# DSP_Header.net
KiCad netlist of a schematic drawn in Altium Designer
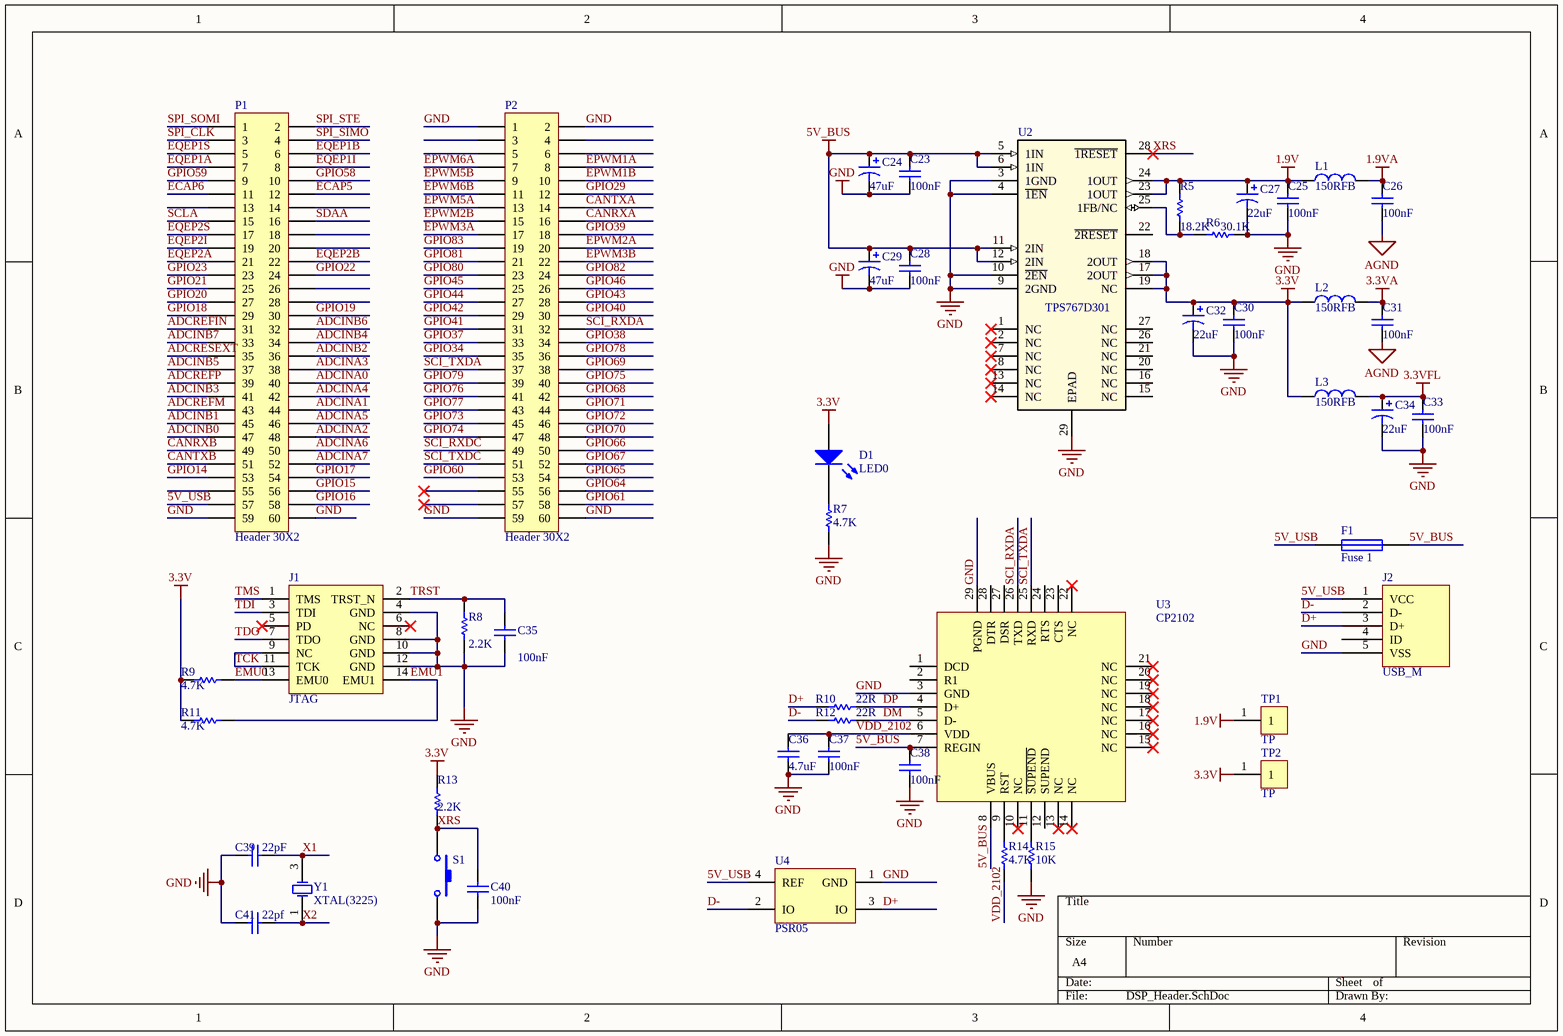
[diagram p0: DSP_Header.SchDoc]

(export (version "E")
  (design (tool "Eeschema 10.0.6"))
  (components
    (comp (ref "C23")
      (value "100nF")
      (footprint "C0603")
      (description "Capacitor")
      (fields (field (name "Comment") "Cap") (field (name "PUBLISHER") "Altium Limited"))
      (libsource (lib "Miscellaneous Devices") (part "Cap"))
    )
    (comp (ref "C24")
      (value "47uF")
      (footprint "C0805")
      (description "Polarized Capacitor (Surface Mount)")
      (fields (field (name "Comment") "Cap Pol3") (field (name "PUBLISHER") "Altium Limited"))
      (libsource (lib "Miscellaneous Devices") (part "Cap Pol3"))
    )
    (comp (ref "C25")
      (value "100nF")
      (footprint "C0603")
      (description "Capacitor")
      (fields (field (name "Comment") "Cap") (field (name "PUBLISHER") "Altium Limited"))
      (libsource (lib "Miscellaneous Devices") (part "Cap"))
    )
    (comp (ref "C26")
      (value "100nF")
      (footprint "C0603")
      (description "Capacitor")
      (fields (field (name "Comment") "Cap") (field (name "PUBLISHER") "Altium Limited"))
      (libsource (lib "Miscellaneous Devices") (part "Cap"))
    )
    (comp (ref "C27")
      (value "22uF")
      (footprint "C0805")
      (description "Polarized Capacitor (Surface Mount)")
      (fields (field (name "Comment") "Cap Pol3") (field (name "PUBLISHER") "Altium Limited"))
      (libsource (lib "Miscellaneous Devices") (part "Cap Pol3"))
    )
    (comp (ref "C28")
      (value "100nF")
      (footprint "C0603")
      (description "Capacitor")
      (fields (field (name "Comment") "Cap") (field (name "PUBLISHER") "Altium Limited"))
      (libsource (lib "Miscellaneous Devices") (part "Cap"))
    )
    (comp (ref "C29")
      (value "47uF")
      (footprint "C0805")
      (description "Polarized Capacitor (Surface Mount)")
      (fields (field (name "Comment") "Cap Pol3") (field (name "PUBLISHER") "Altium Limited"))
      (libsource (lib "Miscellaneous Devices") (part "Cap Pol3"))
    )
    (comp (ref "C30")
      (value "100nF")
      (footprint "C0603")
      (description "Capacitor")
      (fields (field (name "Comment") "Cap") (field (name "PUBLISHER") "Altium Limited"))
      (libsource (lib "Miscellaneous Devices") (part "Cap"))
    )
    (comp (ref "C31")
      (value "100nF")
      (footprint "C0603")
      (description "Capacitor")
      (fields (field (name "Comment") "Cap") (field (name "PUBLISHER") "Altium Limited"))
      (libsource (lib "Miscellaneous Devices") (part "Cap"))
    )
    (comp (ref "C32")
      (value "22uF")
      (footprint "C0805")
      (description "Polarized Capacitor (Surface Mount)")
      (fields (field (name "Comment") "Cap Pol3") (field (name "PUBLISHER") "Altium Limited"))
      (libsource (lib "Miscellaneous Devices") (part "Cap Pol3"))
    )
    (comp (ref "C33")
      (value "100nF")
      (footprint "C0603")
      (description "Capacitor")
      (fields (field (name "Comment") "Cap") (field (name "PUBLISHER") "Altium Limited"))
      (libsource (lib "Miscellaneous Devices") (part "Cap"))
    )
    (comp (ref "C34")
      (value "22uF")
      (footprint "C0805")
      (description "Polarized Capacitor (Surface Mount)")
      (fields (field (name "Comment") "Cap Pol3") (field (name "PUBLISHER") "Altium Limited"))
      (libsource (lib "Miscellaneous Devices") (part "Cap Pol3"))
    )
    (comp (ref "C35")
      (value "100nF")
      (footprint "C0603")
      (description "Capacitor")
      (fields (field (name "Comment") "Cap") (field (name "PUBLISHER") "Altium Limited"))
      (libsource (lib "Miscellaneous Devices") (part "Cap"))
    )
    (comp (ref "C36")
      (value "4.7uF")
      (footprint "C0603")
      (description "Capacitor")
      (fields (field (name "Comment") "Cap") (field (name "PUBLISHER") "Altium Limited"))
      (libsource (lib "Miscellaneous Devices") (part "Cap"))
    )
    (comp (ref "C37")
      (value "100nF")
      (footprint "C0603")
      (description "Capacitor")
      (fields (field (name "Comment") "Cap") (field (name "PUBLISHER") "Altium Limited"))
      (libsource (lib "Miscellaneous Devices") (part "Cap"))
    )
    (comp (ref "C38")
      (value "100nF")
      (footprint "C0603")
      (description "Capacitor")
      (fields (field (name "Comment") "Cap") (field (name "PUBLISHER") "Altium Limited"))
      (libsource (lib "Miscellaneous Devices") (part "Cap"))
    )
    (comp (ref "C39")
      (value "22pF")
      (footprint "C0603")
      (description "Capacitor")
      (fields (field (name "Comment") "Cap") (field (name "PUBLISHER") "Altium Limited"))
      (libsource (lib "Miscellaneous Devices") (part "Cap"))
    )
    (comp (ref "C40")
      (value "100nF")
      (footprint "C0603")
      (description "Capacitor")
      (fields (field (name "Comment") "Cap") (field (name "PUBLISHER") "Altium Limited"))
      (libsource (lib "Miscellaneous Devices") (part "Cap"))
    )
    (comp (ref "C41")
      (value "22pf")
      (footprint "C0603")
      (description "Capacitor")
      (fields (field (name "Comment") "Cap") (field (name "PUBLISHER") "Altium Limited"))
      (libsource (lib "Miscellaneous Devices") (part "Cap"))
    )
    (comp (ref "D1")
      (value "LED0")
      (footprint "0603D")
      (description "Typical INFRARED GaAs LED")
      (fields (field (name "PUBLISHER") "Altium Limited"))
      (libsource (lib "Miscellaneous Devices") (part "LED0"))
    )
    (comp (ref "F1")
      (value "Fuse 1")
      (footprint "0805R")
      (description "Fuse")
      (fields (field (name "PUBLISHER") "Altium Limited"))
      (libsource (lib "Miscellaneous Devices") (part "Fuse 1"))
    )
    (comp (ref "J1") (value "JTAG") (footprint "HDR2X7") (libsource (lib "schlib_by_wjy") (part "JTAG")))
    (comp (ref "J2")
      (value "USB_M")
      (footprint "USB_MICRO_DIP")
      (description "MicroUSB接口")
      (libsource (lib "Fszhang") (part "USB_M"))
    )
    (comp (ref "L1")
      (value "150RFB")
      (footprint "r0603")
      (fields (field (name "Comment") "Inductors"))
      (libsource (lib "schlib_by_wjy") (part "Inductors"))
    )
    (comp (ref "L2")
      (value "150RFB")
      (footprint "r0603")
      (fields (field (name "Comment") "Inductors"))
      (libsource (lib "schlib_by_wjy") (part "Inductors"))
    )
    (comp (ref "L3")
      (value "150RFB")
      (footprint "r0603")
      (fields (field (name "Comment") "Inductors"))
      (libsource (lib "schlib_by_wjy") (part "Inductors"))
    )
    (comp (ref "P1")
      (value "Header 30X2")
      (footprint "0.8BTB_60P")
      (description "Header, 30-Pin, Dual row")
      (fields (field (name "PUBLISHER") "Altium Limited"))
      (libsource (lib "Miscellaneous Connectors") (part "Header 30X2"))
    )
    (comp (ref "P2")
      (value "Header 30X2")
      (footprint "0.8BTB_60P")
      (description "Header, 30-Pin, Dual row")
      (fields (field (name "PUBLISHER") "Altium Limited"))
      (libsource (lib "Miscellaneous Connectors") (part "Header 30X2"))
    )
    (comp (ref "R5")
      (value "18.2K")
      (footprint "r0603")
      (description "Resistor")
      (fields (field (name "Comment") "Res1") (field (name "PUBLISHER") "Altium Limited"))
      (libsource (lib "Miscellaneous Devices") (part "Res1"))
    )
    (comp (ref "R6")
      (value "30.1K")
      (footprint "r0603")
      (description "Resistor")
      (fields (field (name "Comment") "Res1") (field (name "PUBLISHER") "Altium Limited"))
      (libsource (lib "Miscellaneous Devices") (part "Res1"))
    )
    (comp (ref "R7")
      (value "4.7K")
      (footprint "R0603")
      (description "Resistor")
      (fields (field (name "Comment") "Res1") (field (name "PUBLISHER") "Altium Limited"))
      (libsource (lib "Miscellaneous Devices") (part "Res1"))
    )
    (comp (ref "R8")
      (value "2.2K")
      (footprint "r0603")
      (description "Resistor")
      (fields (field (name "Comment") "Res1") (field (name "PUBLISHER") "Altium Limited"))
      (libsource (lib "Miscellaneous Devices") (part "Res1"))
    )
    (comp (ref "R9")
      (value "4.7K")
      (footprint "R0603")
      (description "Resistor")
      (fields (field (name "Comment") "Res1") (field (name "PUBLISHER") "Altium Limited"))
      (libsource (lib "Miscellaneous Devices") (part "Res1"))
    )
    (comp (ref "R10")
      (value "22R")
      (footprint "R0603")
      (description "Resistor")
      (fields (field (name "Comment") "Res1") (field (name "PUBLISHER") "Altium Limited"))
      (libsource (lib "Miscellaneous Devices") (part "Res1"))
    )
    (comp (ref "R11")
      (value "4.7K")
      (footprint "r0603")
      (description "Resistor")
      (fields (field (name "Comment") "Res1") (field (name "PUBLISHER") "Altium Limited"))
      (libsource (lib "Miscellaneous Devices") (part "Res1"))
    )
    (comp (ref "R12")
      (value "22R")
      (footprint "R0603")
      (description "Resistor")
      (fields (field (name "Comment") "Res1") (field (name "PUBLISHER") "Altium Limited"))
      (libsource (lib "Miscellaneous Devices") (part "Res1"))
    )
    (comp (ref "R13")
      (value "2.2K")
      (footprint "r0603")
      (description "Resistor")
      (fields (field (name "Comment") "Res1") (field (name "PUBLISHER") "Altium Limited"))
      (libsource (lib "Miscellaneous Devices") (part "Res1"))
    )
    (comp (ref "R14")
      (value "4.7K")
      (footprint "R0603")
      (description "Resistor")
      (fields (field (name "Comment") "Res1") (field (name "PUBLISHER") "Altium Limited"))
      (libsource (lib "Miscellaneous Devices") (part "Res1"))
    )
    (comp (ref "R15")
      (value "10K")
      (footprint "R0603")
      (description "Resistor")
      (fields (field (name "Comment") "Res1") (field (name "PUBLISHER") "Altium Limited"))
      (libsource (lib "Miscellaneous Devices") (part "Res1"))
    )
    (comp (ref "S1")
      (value "SW-PB")
      (footprint "SW_3*6")
      (description "Switch")
      (fields (field (name "PUBLISHER") "Altium Limited"))
      (libsource (lib "Miscellaneous Devices") (part "SW-PB"))
    )
    (comp (ref "TP1") (value "TP") (footprint "TPJ1.0") (libsource (lib "schlib_by_wjy") (part "TP")))
    (comp (ref "TP2") (value "TP") (footprint "TPJ1.0") (libsource (lib "schlib_by_wjy") (part "TP")))
    (comp (ref "U2")
      (value "TPS767D301")
      (footprint "PWP28_6P46X2P4")
      (description "Imported")
      (fields
        (field (name "MANUFACTURER_PART_NUMBER") "tps767d301-ep_pwp_28")
        (field (name "GENERIC_PART_NUMBER") "TPS767D301-EP")
      )
      (libsource (lib "2017-12-02_16-48-01") (part "TPS767D301"))
    )
    (comp (ref "U3") (value "CP2102") (footprint "QFN28") (libsource (lib "schlib_by_wjy") (part "CP2102")))
    (comp (ref "U4") (value "PSR05") (footprint "SOT143") (libsource (lib "Schlib") (part "PSR05")))
    (comp (ref "Y1")
      (value "XTAL(3225)")
      (footprint "Y3225")
      (description "Crystal Oscillator")
      (fields (field (name "PUBLISHER") "Altium Limited"))
      (libsource (lib "schlib_by_wjy") (part "XTAL(3225)"))
    )
  )
  (nets
    (net (code "1") (name "/5V_USB") (class "Default")
      (node (ref "F1") (pin "1") (pinfunction "1_1") (pintype "passive"))
      (node (ref "J2") (pin "1") (pinfunction "VCC_1") (pintype "passive"))
      (node (ref "P1") (pin "57") (pinfunction "57_57") (pintype "passive"))
      (node (ref "U4") (pin "4") (pinfunction "REF_4") (pintype "passive"))
    )
    (net (code "2") (name "/ADCINA0") (class "Default")
      (node (ref "P1") (pin "40") (pinfunction "40_40") (pintype "passive"))
    )
    (net (code "3") (name "/ADCINA1") (class "Default")
      (node (ref "P1") (pin "44") (pinfunction "44_44") (pintype "passive"))
    )
    (net (code "4") (name "/ADCINA2") (class "Default")
      (node (ref "P1") (pin "48") (pinfunction "48_48") (pintype "passive"))
    )
    (net (code "5") (name "/ADCINA3") (class "Default")
      (node (ref "P1") (pin "38") (pinfunction "38_38") (pintype "passive"))
    )
    (net (code "6") (name "/ADCINA4") (class "Default")
      (node (ref "P1") (pin "42") (pinfunction "42_42") (pintype "passive"))
    )
    (net (code "7") (name "/ADCINA5") (class "Default")
      (node (ref "P1") (pin "46") (pinfunction "46_46") (pintype "passive"))
    )
    (net (code "8") (name "/ADCINA6") (class "Default")
      (node (ref "P1") (pin "50") (pinfunction "50_50") (pintype "passive"))
    )
    (net (code "9") (name "/ADCINA7") (class "Default")
      (node (ref "P1") (pin "52") (pinfunction "52_52") (pintype "passive"))
    )
    (net (code "10") (name "/ADCINB0") (class "Default")
      (node (ref "P1") (pin "47") (pinfunction "47_47") (pintype "passive"))
    )
    (net (code "11") (name "/ADCINB1") (class "Default")
      (node (ref "P1") (pin "45") (pinfunction "45_45") (pintype "passive"))
    )
    (net (code "12") (name "/ADCINB2") (class "Default")
      (node (ref "P1") (pin "36") (pinfunction "36_36") (pintype "passive"))
    )
    (net (code "13") (name "/ADCINB3") (class "Default")
      (node (ref "P1") (pin "41") (pinfunction "41_41") (pintype "passive"))
    )
    (net (code "14") (name "/ADCINB4") (class "Default")
      (node (ref "P1") (pin "34") (pinfunction "34_34") (pintype "passive"))
    )
    (net (code "15") (name "/ADCINB5") (class "Default")
      (node (ref "P1") (pin "37") (pinfunction "37_37") (pintype "passive"))
    )
    (net (code "16") (name "/ADCINB6") (class "Default")
      (node (ref "P1") (pin "32") (pinfunction "32_32") (pintype "passive"))
    )
    (net (code "17") (name "/ADCINB7") (class "Default")
      (node (ref "P1") (pin "33") (pinfunction "33_33") (pintype "passive"))
    )
    (net (code "18") (name "/ADCREFIN") (class "Default")
      (node (ref "P1") (pin "31") (pinfunction "31_31") (pintype "passive"))
    )
    (net (code "19") (name "/ADCREFM") (class "Default")
      (node (ref "P1") (pin "43") (pinfunction "43_43") (pintype "passive"))
    )
    (net (code "20") (name "/ADCREFP") (class "Default")
      (node (ref "P1") (pin "39") (pinfunction "39_39") (pintype "passive"))
    )
    (net (code "21") (name "/ADCRESEXT") (class "Default")
      (node (ref "P1") (pin "35") (pinfunction "35_35") (pintype "passive"))
    )
    (net (code "22") (name "/CANRXA") (class "Default")
      (node (ref "P2") (pin "16") (pinfunction "16_16") (pintype "passive"))
    )
    (net (code "23") (name "/CANRXB") (class "Default")
      (node (ref "P1") (pin "49") (pinfunction "49_49") (pintype "passive"))
    )
    (net (code "24") (name "/CANTXA") (class "Default")
      (node (ref "P2") (pin "14") (pinfunction "14_14") (pintype "passive"))
    )
    (net (code "25") (name "/CANTXB") (class "Default")
      (node (ref "P1") (pin "51") (pinfunction "51_51") (pintype "passive"))
    )
    (net (code "26") (name "/D+") (class "Default")
      (node (ref "J2") (pin "3") (pinfunction "D+_3") (pintype "passive"))
      (node (ref "R10") (pin "2") (pinfunction "2_2") (pintype "passive"))
      (node (ref "U4") (pin "3") (pinfunction "IO_3") (pintype "passive"))
    )
    (net (code "27") (name "/D-") (class "Default")
      (node (ref "J2") (pin "2") (pinfunction "D-_2") (pintype "passive"))
      (node (ref "R12") (pin "1") (pinfunction "1_1") (pintype "passive"))
      (node (ref "U4") (pin "2") (pinfunction "IO_2") (pintype "passive"))
    )
    (net (code "28") (name "/DM") (class "Default")
      (node (ref "R12") (pin "2") (pinfunction "2_2") (pintype "passive"))
      (node (ref "U3") (pin "5") (pinfunction "D-_5") (pintype "passive"))
    )
    (net (code "29") (name "/DP") (class "Default")
      (node (ref "R10") (pin "1") (pinfunction "1_1") (pintype "passive"))
      (node (ref "U3") (pin "4") (pinfunction "D+_4") (pintype "passive"))
    )
    (net (code "30") (name "/ECAP5") (class "Default")
      (node (ref "P1") (pin "12") (pinfunction "12_12") (pintype "passive"))
    )
    (net (code "31") (name "/ECAP6") (class "Default")
      (node (ref "P1") (pin "11") (pinfunction "11_11") (pintype "passive"))
    )
    (net (code "32") (name "/EMU0") (class "Default")
      (node (ref "J1") (pin "13") (pinfunction "EMU0_13") (pintype "passive"))
      (node (ref "R9") (pin "1") (pinfunction "1_1") (pintype "passive"))
    )
    (net (code "33") (name "/EMU1") (class "Default")
      (node (ref "J1") (pin "14") (pinfunction "EMU1_14") (pintype "passive"))
      (node (ref "R11") (pin "1") (pinfunction "1_1") (pintype "passive"))
    )
    (net (code "34") (name "/EPWM1A") (class "Default")
      (node (ref "P2") (pin "8") (pinfunction "8_8") (pintype "passive"))
    )
    (net (code "35") (name "/EPWM1B") (class "Default")
      (node (ref "P2") (pin "10") (pinfunction "10_10") (pintype "passive"))
    )
    (net (code "36") (name "/EPWM2A") (class "Default")
      (node (ref "P2") (pin "20") (pinfunction "20_20") (pintype "passive"))
    )
    (net (code "37") (name "/EPWM2B") (class "Default")
      (node (ref "P2") (pin "15") (pinfunction "15_15") (pintype "passive"))
    )
    (net (code "38") (name "/EPWM3A") (class "Default")
      (node (ref "P2") (pin "17") (pinfunction "17_17") (pintype "passive"))
    )
    (net (code "39") (name "/EPWM3B") (class "Default")
      (node (ref "P2") (pin "22") (pinfunction "22_22") (pintype "passive"))
    )
    (net (code "40") (name "/EPWM5A") (class "Default")
      (node (ref "P2") (pin "13") (pinfunction "13_13") (pintype "passive"))
    )
    (net (code "41") (name "/EPWM5B") (class "Default")
      (node (ref "P2") (pin "9") (pinfunction "9_9") (pintype "passive"))
    )
    (net (code "42") (name "/EPWM6A") (class "Default")
      (node (ref "P2") (pin "7") (pinfunction "7_7") (pintype "passive"))
    )
    (net (code "43") (name "/EPWM6B") (class "Default")
      (node (ref "P2") (pin "11") (pinfunction "11_11") (pintype "passive"))
    )
    (net (code "44") (name "/EQEP1A") (class "Default")
      (node (ref "P1") (pin "7") (pinfunction "7_7") (pintype "passive"))
    )
    (net (code "45") (name "/EQEP1B") (class "Default")
      (node (ref "P1") (pin "6") (pinfunction "6_6") (pintype "passive"))
    )
    (net (code "46") (name "/EQEP1I") (class "Default")
      (node (ref "P1") (pin "8") (pinfunction "8_8") (pintype "passive"))
    )
    (net (code "47") (name "/EQEP1S") (class "Default")
      (node (ref "P1") (pin "5") (pinfunction "5_5") (pintype "passive"))
    )
    (net (code "48") (name "/EQEP2A") (class "Default")
      (node (ref "P1") (pin "21") (pinfunction "21_21") (pintype "passive"))
    )
    (net (code "49") (name "/EQEP2B") (class "Default")
      (node (ref "P1") (pin "22") (pinfunction "22_22") (pintype "passive"))
    )
    (net (code "50") (name "/EQEP2I") (class "Default")
      (node (ref "P1") (pin "19") (pinfunction "19_19") (pintype "passive"))
    )
    (net (code "51") (name "/EQEP2S") (class "Default")
      (node (ref "P1") (pin "17") (pinfunction "17_17") (pintype "passive"))
    )
    (net (code "52") (name "/GPIO14") (class "Default")
      (node (ref "P1") (pin "53") (pinfunction "53_53") (pintype "passive"))
    )
    (net (code "53") (name "/GPIO15") (class "Default")
      (node (ref "P1") (pin "56") (pinfunction "56_56") (pintype "passive"))
    )
    (net (code "54") (name "/GPIO16") (class "Default")
      (node (ref "P1") (pin "58") (pinfunction "58_58") (pintype "passive"))
    )
    (net (code "55") (name "/GPIO17") (class "Default")
      (node (ref "P1") (pin "54") (pinfunction "54_54") (pintype "passive"))
    )
    (net (code "56") (name "/GPIO18") (class "Default")
      (node (ref "P1") (pin "29") (pinfunction "29_29") (pintype "passive"))
    )
    (net (code "57") (name "/GPIO19") (class "Default")
      (node (ref "P1") (pin "30") (pinfunction "30_30") (pintype "passive"))
    )
    (net (code "58") (name "/GPIO20") (class "Default")
      (node (ref "P1") (pin "27") (pinfunction "27_27") (pintype "passive"))
    )
    (net (code "59") (name "/GPIO21") (class "Default")
      (node (ref "P1") (pin "25") (pinfunction "25_25") (pintype "passive"))
    )
    (net (code "60") (name "/GPIO22") (class "Default")
      (node (ref "P1") (pin "24") (pinfunction "24_24") (pintype "passive"))
    )
    (net (code "61") (name "/GPIO23") (class "Default")
      (node (ref "P1") (pin "23") (pinfunction "23_23") (pintype "passive"))
    )
    (net (code "62") (name "/GPIO29") (class "Default")
      (node (ref "P2") (pin "12") (pinfunction "12_12") (pintype "passive"))
    )
    (net (code "63") (name "/GPIO34") (class "Default")
      (node (ref "P2") (pin "35") (pinfunction "35_35") (pintype "passive"))
    )
    (net (code "64") (name "/GPIO37") (class "Default")
      (node (ref "P2") (pin "33") (pinfunction "33_33") (pintype "passive"))
    )
    (net (code "65") (name "/GPIO38") (class "Default")
      (node (ref "P2") (pin "34") (pinfunction "34_34") (pintype "passive"))
    )
    (net (code "66") (name "/GPIO39") (class "Default")
      (node (ref "P2") (pin "18") (pinfunction "18_18") (pintype "passive"))
    )
    (net (code "67") (name "/GPIO40") (class "Default")
      (node (ref "P2") (pin "30") (pinfunction "30_30") (pintype "passive"))
    )
    (net (code "68") (name "/GPIO41") (class "Default")
      (node (ref "P2") (pin "31") (pinfunction "31_31") (pintype "passive"))
    )
    (net (code "69") (name "/GPIO42") (class "Default")
      (node (ref "P2") (pin "29") (pinfunction "29_29") (pintype "passive"))
    )
    (net (code "70") (name "/GPIO43") (class "Default")
      (node (ref "P2") (pin "28") (pinfunction "28_28") (pintype "passive"))
    )
    (net (code "71") (name "/GPIO44") (class "Default")
      (node (ref "P2") (pin "27") (pinfunction "27_27") (pintype "passive"))
    )
    (net (code "72") (name "/GPIO45") (class "Default")
      (node (ref "P2") (pin "25") (pinfunction "25_25") (pintype "passive"))
    )
    (net (code "73") (name "/GPIO46") (class "Default")
      (node (ref "P2") (pin "26") (pinfunction "26_26") (pintype "passive"))
    )
    (net (code "74") (name "/GPIO58") (class "Default")
      (node (ref "P1") (pin "10") (pinfunction "10_10") (pintype "passive"))
    )
    (net (code "75") (name "/GPIO59") (class "Default")
      (node (ref "P1") (pin "9") (pinfunction "9_9") (pintype "passive"))
    )
    (net (code "76") (name "/GPIO60") (class "Default")
      (node (ref "P2") (pin "53") (pinfunction "53_53") (pintype "passive"))
    )
    (net (code "77") (name "/GPIO61") (class "Default")
      (node (ref "P2") (pin "58") (pinfunction "58_58") (pintype "passive"))
    )
    (net (code "78") (name "/GPIO64") (class "Default")
      (node (ref "P2") (pin "56") (pinfunction "56_56") (pintype "passive"))
    )
    (net (code "79") (name "/GPIO65") (class "Default")
      (node (ref "P2") (pin "54") (pinfunction "54_54") (pintype "passive"))
    )
    (net (code "80") (name "/GPIO66") (class "Default")
      (node (ref "P2") (pin "50") (pinfunction "50_50") (pintype "passive"))
    )
    (net (code "81") (name "/GPIO67") (class "Default")
      (node (ref "P2") (pin "52") (pinfunction "52_52") (pintype "passive"))
    )
    (net (code "82") (name "/GPIO68") (class "Default")
      (node (ref "P2") (pin "42") (pinfunction "42_42") (pintype "passive"))
    )
    (net (code "83") (name "/GPIO69") (class "Default")
      (node (ref "P2") (pin "38") (pinfunction "38_38") (pintype "passive"))
    )
    (net (code "84") (name "/GPIO70") (class "Default")
      (node (ref "P2") (pin "48") (pinfunction "48_48") (pintype "passive"))
    )
    (net (code "85") (name "/GPIO71") (class "Default")
      (node (ref "P2") (pin "44") (pinfunction "44_44") (pintype "passive"))
    )
    (net (code "86") (name "/GPIO72") (class "Default")
      (node (ref "P2") (pin "46") (pinfunction "46_46") (pintype "passive"))
    )
    (net (code "87") (name "/GPIO73") (class "Default")
      (node (ref "P2") (pin "45") (pinfunction "45_45") (pintype "passive"))
    )
    (net (code "88") (name "/GPIO74") (class "Default")
      (node (ref "P2") (pin "47") (pinfunction "47_47") (pintype "passive"))
    )
    (net (code "89") (name "/GPIO75") (class "Default")
      (node (ref "P2") (pin "40") (pinfunction "40_40") (pintype "passive"))
    )
    (net (code "90") (name "/GPIO76") (class "Default")
      (node (ref "P2") (pin "41") (pinfunction "41_41") (pintype "passive"))
    )
    (net (code "91") (name "/GPIO77") (class "Default")
      (node (ref "P2") (pin "43") (pinfunction "43_43") (pintype "passive"))
    )
    (net (code "92") (name "/GPIO78") (class "Default")
      (node (ref "P2") (pin "36") (pinfunction "36_36") (pintype "passive"))
    )
    (net (code "93") (name "/GPIO79") (class "Default")
      (node (ref "P2") (pin "39") (pinfunction "39_39") (pintype "passive"))
    )
    (net (code "94") (name "/GPIO80") (class "Default")
      (node (ref "P2") (pin "23") (pinfunction "23_23") (pintype "passive"))
    )
    (net (code "95") (name "/GPIO81") (class "Default")
      (node (ref "P2") (pin "21") (pinfunction "21_21") (pintype "passive"))
    )
    (net (code "96") (name "/GPIO82") (class "Default")
      (node (ref "P2") (pin "24") (pinfunction "24_24") (pintype "passive"))
    )
    (net (code "97") (name "/GPIO83") (class "Default")
      (node (ref "P2") (pin "19") (pinfunction "19_19") (pintype "passive"))
    )
    (net (code "98") (name "/SCI_RXDA") (class "Default")
      (node (ref "P2") (pin "32") (pinfunction "32_32") (pintype "passive"))
      (node (ref "U3") (pin "26") (pinfunction "TXD_26") (pintype "passive"))
    )
    (net (code "99") (name "/SCI_RXDC") (class "Default")
      (node (ref "P2") (pin "49") (pinfunction "49_49") (pintype "passive"))
    )
    (net (code "100") (name "/SCI_TXDA") (class "Default")
      (node (ref "P2") (pin "37") (pinfunction "37_37") (pintype "passive"))
      (node (ref "U3") (pin "25") (pinfunction "RXD_25") (pintype "passive"))
    )
    (net (code "101") (name "/SCI_TXDC") (class "Default")
      (node (ref "P2") (pin "51") (pinfunction "51_51") (pintype "passive"))
    )
    (net (code "102") (name "/SCLA") (class "Default")
      (node (ref "P1") (pin "15") (pinfunction "15_15") (pintype "passive"))
    )
    (net (code "103") (name "/SDAA") (class "Default")
      (node (ref "P1") (pin "16") (pinfunction "16_16") (pintype "passive"))
    )
    (net (code "104") (name "/SPI_CLK") (class "Default")
      (node (ref "P1") (pin "3") (pinfunction "3_3") (pintype "passive"))
    )
    (net (code "105") (name "/SPI_SIMO") (class "Default")
      (node (ref "P1") (pin "4") (pinfunction "4_4") (pintype "passive"))
    )
    (net (code "106") (name "/SPI_SOMI") (class "Default")
      (node (ref "P1") (pin "1") (pinfunction "1_1") (pintype "passive"))
    )
    (net (code "107") (name "/SPI_STE") (class "Default")
      (node (ref "P1") (pin "2") (pinfunction "2_2") (pintype "passive"))
    )
    (net (code "108") (name "/TCK") (class "Default")
      (node (ref "J1") (pin "11") (pinfunction "TCK_11") (pintype "passive"))
      (node (ref "J1") (pin "9") (pinfunction "NC_9") (pintype "passive"))
    )
    (net (code "109") (name "/TDI") (class "Default")
      (node (ref "J1") (pin "3") (pinfunction "TDI_3") (pintype "passive"))
    )
    (net (code "110") (name "/TDO") (class "Default")
      (node (ref "J1") (pin "7") (pinfunction "TDO_7") (pintype "passive"))
    )
    (net (code "111") (name "/TMS") (class "Default")
      (node (ref "J1") (pin "1") (pinfunction "TMS_1") (pintype "passive"))
    )
    (net (code "112") (name "/TRST") (class "Default")
      (node (ref "C35") (pin "2") (pinfunction "2_2") (pintype "passive"))
      (node (ref "J1") (pin "2") (pinfunction "TRST_N_2") (pintype "passive"))
      (node (ref "R8") (pin "2") (pinfunction "2_2") (pintype "passive"))
    )
    (net (code "113") (name "/VDD_2102") (class "Default")
      (node (ref "C36") (pin "2") (pinfunction "2_2") (pintype "passive"))
      (node (ref "C37") (pin "2") (pinfunction "2_2") (pintype "passive"))
      (node (ref "R14") (pin "2") (pinfunction "2_2") (pintype "passive"))
      (node (ref "U3") (pin "6") (pinfunction "VDD_6") (pintype "passive"))
    )
    (net (code "114") (name "/X1") (class "Default")
      (node (ref "C39") (pin "1") (pinfunction "1_1") (pintype "passive"))
      (node (ref "Y1") (pin "3") (pinfunction "OSC2_3") (pintype "passive"))
    )
    (net (code "115") (name "/X2") (class "Default")
      (node (ref "C41") (pin "1") (pinfunction "1_1") (pintype "passive"))
      (node (ref "Y1") (pin "1") (pinfunction "OSC1_1") (pintype "passive"))
    )
    (net (code "116") (name "/XRS") (class "Default")
      (node (ref "C40") (pin "1") (pinfunction "1_1") (pintype "passive"))
      (node (ref "R13") (pin "1") (pinfunction "1_1") (pintype "passive"))
      (node (ref "S1") (pin "1") (pinfunction "1_1") (pintype "passive"))
      (node (ref "U2") (pin "28") (pinfunction "~{1RESET}_28") (pintype "passive"))
    )
    (net (code "117") (name "1.9V") (class "Default")
      (node (ref "C25") (pin "2") (pinfunction "2_2") (pintype "passive"))
      (node (ref "C27") (pin "1") (pinfunction "1_1") (pintype "passive"))
      (node (ref "L1") (pin "1") (pinfunction "1_1") (pintype "passive"))
      (node (ref "R5") (pin "2") (pinfunction "2_2") (pintype "passive"))
      (node (ref "TP1") (pin "1") (pinfunction "1_1") (pintype "passive"))
      (node (ref "U2") (pin "23") (pinfunction "1OUT_23") (pintype "output"))
      (node (ref "U2") (pin "24") (pinfunction "1OUT_24") (pintype "output"))
    )
    (net (code "118") (name "1.9VA") (class "Default")
      (node (ref "C26") (pin "2") (pinfunction "2_2") (pintype "passive"))
      (node (ref "L1") (pin "2") (pinfunction "2_2") (pintype "passive"))
    )
    (net (code "119") (name "3.3V") (class "Default")
      (node (ref "C30") (pin "2") (pinfunction "2_2") (pintype "passive"))
      (node (ref "C32") (pin "1") (pinfunction "1_1") (pintype "passive"))
      (node (ref "D1") (pin "1") (pinfunction "A_1") (pintype "passive"))
      (node (ref "L2") (pin "1") (pinfunction "1_1") (pintype "passive"))
      (node (ref "L3") (pin "1") (pinfunction "1_1") (pintype "passive"))
      (node (ref "R11") (pin "2") (pinfunction "2_2") (pintype "passive"))
      (node (ref "R13") (pin "2") (pinfunction "2_2") (pintype "passive"))
      (node (ref "R9") (pin "2") (pinfunction "2_2") (pintype "passive"))
      (node (ref "TP2") (pin "1") (pinfunction "1_1") (pintype "passive"))
      (node (ref "U2") (pin "17") (pinfunction "2OUT_17") (pintype "output"))
      (node (ref "U2") (pin "18") (pinfunction "2OUT_18") (pintype "output"))
      (node (ref "U2") (pin "19") (pinfunction "NC_19") (pintype "passive"))
    )
    (net (code "120") (name "3.3VA") (class "Default")
      (node (ref "C31") (pin "2") (pinfunction "2_2") (pintype "passive"))
      (node (ref "L2") (pin "2") (pinfunction "2_2") (pintype "passive"))
    )
    (net (code "121") (name "3.3VFL") (class "Default")
      (node (ref "C33") (pin "2") (pinfunction "2_2") (pintype "passive"))
      (node (ref "C34") (pin "1") (pinfunction "1_1") (pintype "passive"))
      (node (ref "L3") (pin "2") (pinfunction "2_2") (pintype "passive"))
    )
    (net (code "122") (name "5V_BUS") (class "Default")
      (node (ref "C23") (pin "2") (pinfunction "2_2") (pintype "passive"))
      (node (ref "C24") (pin "1") (pinfunction "1_1") (pintype "passive"))
      (node (ref "C28") (pin "2") (pinfunction "2_2") (pintype "passive"))
      (node (ref "C29") (pin "1") (pinfunction "1_1") (pintype "passive"))
      (node (ref "C38") (pin "2") (pinfunction "2_2") (pintype "passive"))
      (node (ref "F1") (pin "2") (pinfunction "2_2") (pintype "passive"))
      (node (ref "U2") (pin "11") (pinfunction "2IN_11") (pintype "input"))
      (node (ref "U2") (pin "12") (pinfunction "2IN_12") (pintype "input"))
      (node (ref "U2") (pin "5") (pinfunction "1IN_5") (pintype "input"))
      (node (ref "U2") (pin "6") (pinfunction "1IN_6") (pintype "input"))
      (node (ref "U3") (pin "7") (pinfunction "REGIN_7") (pintype "passive"))
      (node (ref "U3") (pin "8") (pinfunction "VBUS_8") (pintype "passive"))
    )
    (net (code "123") (name "AGND") (class "Default")
      (node (ref "C26") (pin "1") (pinfunction "1_1") (pintype "passive"))
      (node (ref "C31") (pin "1") (pinfunction "1_1") (pintype "passive"))
    )
    (net (code "124") (name "GND") (class "Default")
      (node (ref "C23") (pin "1") (pinfunction "1_1") (pintype "passive"))
      (node (ref "C24") (pin "2") (pinfunction "2_2") (pintype "passive"))
      (node (ref "C25") (pin "1") (pinfunction "1_1") (pintype "passive"))
      (node (ref "C27") (pin "2") (pinfunction "2_2") (pintype "passive"))
      (node (ref "C28") (pin "1") (pinfunction "1_1") (pintype "passive"))
      (node (ref "C29") (pin "2") (pinfunction "2_2") (pintype "passive"))
      (node (ref "C30") (pin "1") (pinfunction "1_1") (pintype "passive"))
      (node (ref "C32") (pin "2") (pinfunction "2_2") (pintype "passive"))
      (node (ref "C33") (pin "1") (pinfunction "1_1") (pintype "passive"))
      (node (ref "C34") (pin "2") (pinfunction "2_2") (pintype "passive"))
      (node (ref "C35") (pin "1") (pinfunction "1_1") (pintype "passive"))
      (node (ref "C36") (pin "1") (pinfunction "1_1") (pintype "passive"))
      (node (ref "C37") (pin "1") (pinfunction "1_1") (pintype "passive"))
      (node (ref "C38") (pin "1") (pinfunction "1_1") (pintype "passive"))
      (node (ref "C39") (pin "2") (pinfunction "2_2") (pintype "passive"))
      (node (ref "C40") (pin "2") (pinfunction "2_2") (pintype "passive"))
      (node (ref "C41") (pin "2") (pinfunction "2_2") (pintype "passive"))
      (node (ref "J1") (pin "10") (pinfunction "GND_10") (pintype "passive"))
      (node (ref "J1") (pin "12") (pinfunction "GND_12") (pintype "passive"))
      (node (ref "J1") (pin "4") (pinfunction "GND_4") (pintype "passive"))
      (node (ref "J1") (pin "8") (pinfunction "GND_8") (pintype "passive"))
      (node (ref "J2") (pin "5") (pinfunction "VSS_5") (pintype "passive"))
      (node (ref "P1") (pin "59") (pinfunction "59_59") (pintype "passive"))
      (node (ref "P1") (pin "60") (pinfunction "60_60") (pintype "passive"))
      (node (ref "P2") (pin "1") (pinfunction "1_1") (pintype "passive"))
      (node (ref "P2") (pin "2") (pinfunction "2_2") (pintype "passive"))
      (node (ref "P2") (pin "59") (pinfunction "59_59") (pintype "passive"))
      (node (ref "P2") (pin "60") (pinfunction "60_60") (pintype "passive"))
      (node (ref "R15") (pin "2") (pinfunction "2_2") (pintype "passive"))
      (node (ref "R6") (pin "1") (pinfunction "1_1") (pintype "passive"))
      (node (ref "R7") (pin "2") (pinfunction "2_2") (pintype "passive"))
      (node (ref "R8") (pin "1") (pinfunction "1_1") (pintype "passive"))
      (node (ref "S1") (pin "2") (pinfunction "2_2") (pintype "passive"))
      (node (ref "U2") (pin "10") (pinfunction "~{2EN}_10") (pintype "passive"))
      (node (ref "U2") (pin "29") (pinfunction "EPAD_29") (pintype "passive"))
      (node (ref "U2") (pin "3") (pinfunction "1GND_3") (pintype "power_in"))
      (node (ref "U2") (pin "4") (pinfunction "~{1EN}_4") (pintype "passive"))
      (node (ref "U2") (pin "9") (pinfunction "2GND_9") (pintype "power_in"))
      (node (ref "U3") (pin "29") (pinfunction "PGND_29") (pintype "passive"))
      (node (ref "U3") (pin "3") (pinfunction "GND_3") (pintype "passive"))
      (node (ref "U4") (pin "1") (pinfunction "GND_1") (pintype "passive"))
    )
    (net (code "125") (name "Net-(D1-K)") (class "Default")
      (node (ref "D1") (pin "2") (pinfunction "K_2") (pintype "passive"))
      (node (ref "R7") (pin "1") (pinfunction "1_1") (pintype "passive"))
    )
    (net (code "126") (name "Net-(U2-1FB{slash}NC)") (class "Default")
      (node (ref "R5") (pin "1") (pinfunction "1_1") (pintype "passive"))
      (node (ref "R6") (pin "2") (pinfunction "2_2") (pintype "passive"))
      (node (ref "U2") (pin "25") (pinfunction "1FB/NC_25") (pintype "bidirectional"))
    )
    (net (code "127") (name "Net-(U3-RST)") (class "Default")
      (node (ref "R14") (pin "1") (pinfunction "1_1") (pintype "passive"))
      (node (ref "U3") (pin "9") (pinfunction "RST_9") (pintype "passive"))
    )
    (net (code "128") (name "Net-(U3-~{SUPEND})") (class "Default")
      (node (ref "R15") (pin "1") (pinfunction "1_1") (pintype "passive"))
      (node (ref "U3") (pin "11") (pinfunction "~{SUPEND}_11") (pintype "passive"))
    )
    (net (code "129") (name "unconnected-(J1-NC-Pad6)") (class "Default")
      (node (ref "J1") (pin "6") (pinfunction "NC_6") (pintype "passive+no_connect"))
    )
    (net (code "130") (name "unconnected-(J1-PD-Pad5)") (class "Default")
      (node (ref "J1") (pin "5") (pinfunction "PD_5") (pintype "passive+no_connect"))
    )
    (net (code "131") (name "unconnected-(J2-ID-Pad4)") (class "Default")
      (node (ref "J2") (pin "4") (pinfunction "ID_4") (pintype "passive"))
    )
    (net (code "132") (name "unconnected-(P1-Pad13)") (class "Default")
      (node (ref "P1") (pin "13") (pinfunction "13_13") (pintype "passive"))
    )
    (net (code "133") (name "unconnected-(P1-Pad14)") (class "Default")
      (node (ref "P1") (pin "14") (pinfunction "14_14") (pintype "passive"))
    )
    (net (code "134") (name "unconnected-(P1-Pad18)") (class "Default")
      (node (ref "P1") (pin "18") (pinfunction "18_18") (pintype "passive"))
    )
    (net (code "135") (name "unconnected-(P1-Pad20)") (class "Default")
      (node (ref "P1") (pin "20") (pinfunction "20_20") (pintype "passive"))
    )
    (net (code "136") (name "unconnected-(P1-Pad26)") (class "Default")
      (node (ref "P1") (pin "26") (pinfunction "26_26") (pintype "passive"))
    )
    (net (code "137") (name "unconnected-(P1-Pad28)") (class "Default")
      (node (ref "P1") (pin "28") (pinfunction "28_28") (pintype "passive"))
    )
    (net (code "138") (name "unconnected-(P1-Pad55)") (class "Default")
      (node (ref "P1") (pin "55") (pinfunction "55_55") (pintype "passive"))
    )
    (net (code "139") (name "unconnected-(P2-Pad3)") (class "Default")
      (node (ref "P2") (pin "3") (pinfunction "3_3") (pintype "passive"))
    )
    (net (code "140") (name "unconnected-(P2-Pad4)") (class "Default")
      (node (ref "P2") (pin "4") (pinfunction "4_4") (pintype "passive"))
    )
    (net (code "141") (name "unconnected-(P2-Pad5)") (class "Default")
      (node (ref "P2") (pin "5") (pinfunction "5_5") (pintype "passive"))
    )
    (net (code "142") (name "unconnected-(P2-Pad6)") (class "Default")
      (node (ref "P2") (pin "6") (pinfunction "6_6") (pintype "passive"))
    )
    (net (code "143") (name "unconnected-(P2-Pad55)") (class "Default")
      (node (ref "P2") (pin "55") (pinfunction "55_55") (pintype "passive+no_connect"))
    )
    (net (code "144") (name "unconnected-(P2-Pad57)") (class "Default")
      (node (ref "P2") (pin "57") (pinfunction "57_57") (pintype "passive+no_connect"))
    )
    (net (code "145") (name "unconnected-(U2-NC-Pad1)") (class "Default")
      (node (ref "U2") (pin "1") (pinfunction "NC_1") (pintype "passive+no_connect"))
    )
    (net (code "146") (name "unconnected-(U2-NC-Pad2)") (class "Default")
      (node (ref "U2") (pin "2") (pinfunction "NC_2") (pintype "passive+no_connect"))
    )
    (net (code "147") (name "unconnected-(U2-NC-Pad7)") (class "Default")
      (node (ref "U2") (pin "7") (pinfunction "NC_7") (pintype "passive+no_connect"))
    )
    (net (code "148") (name "unconnected-(U2-NC-Pad8)") (class "Default")
      (node (ref "U2") (pin "8") (pinfunction "NC_8") (pintype "passive+no_connect"))
    )
    (net (code "149") (name "unconnected-(U2-NC-Pad13)") (class "Default")
      (node (ref "U2") (pin "13") (pinfunction "NC_13") (pintype "passive+no_connect"))
    )
    (net (code "150") (name "unconnected-(U2-NC-Pad14)") (class "Default")
      (node (ref "U2") (pin "14") (pinfunction "NC_14") (pintype "passive+no_connect"))
    )
    (net (code "151") (name "unconnected-(U2-NC-Pad15)") (class "Default")
      (node (ref "U2") (pin "15") (pinfunction "NC_15") (pintype "passive"))
    )
    (net (code "152") (name "unconnected-(U2-NC-Pad16)") (class "Default")
      (node (ref "U2") (pin "16") (pinfunction "NC_16") (pintype "passive"))
    )
    (net (code "153") (name "unconnected-(U2-NC-Pad20)") (class "Default")
      (node (ref "U2") (pin "20") (pinfunction "NC_20") (pintype "passive"))
    )
    (net (code "154") (name "unconnected-(U2-NC-Pad21)") (class "Default")
      (node (ref "U2") (pin "21") (pinfunction "NC_21") (pintype "passive"))
    )
    (net (code "155") (name "unconnected-(U2-NC-Pad26)") (class "Default")
      (node (ref "U2") (pin "26") (pinfunction "NC_26") (pintype "passive"))
    )
    (net (code "156") (name "unconnected-(U2-NC-Pad27)") (class "Default")
      (node (ref "U2") (pin "27") (pinfunction "NC_27") (pintype "passive"))
    )
    (net (code "157") (name "unconnected-(U2-~{2RESET}-Pad22)") (class "Default")
      (node (ref "U2") (pin "22") (pinfunction "~{2RESET}_22") (pintype "passive"))
    )
    (net (code "158") (name "unconnected-(U3-CTS-Pad23)") (class "Default")
      (node (ref "U3") (pin "23") (pinfunction "CTS_23") (pintype "passive"))
    )
    (net (code "159") (name "unconnected-(U3-DCD-Pad1)") (class "Default")
      (node (ref "U3") (pin "1") (pinfunction "DCD_1") (pintype "passive"))
    )
    (net (code "160") (name "unconnected-(U3-DSR-Pad27)") (class "Default")
      (node (ref "U3") (pin "27") (pinfunction "DSR_27") (pintype "passive"))
    )
    (net (code "161") (name "unconnected-(U3-DTR-Pad28)") (class "Default")
      (node (ref "U3") (pin "28") (pinfunction "DTR_28") (pintype "passive"))
    )
    (net (code "162") (name "unconnected-(U3-NC-Pad10)") (class "Default")
      (node (ref "U3") (pin "10") (pinfunction "NC_10") (pintype "passive+no_connect"))
    )
    (net (code "163") (name "unconnected-(U3-NC-Pad13)") (class "Default")
      (node (ref "U3") (pin "13") (pinfunction "NC_13") (pintype "passive+no_connect"))
    )
    (net (code "164") (name "unconnected-(U3-NC-Pad14)") (class "Default")
      (node (ref "U3") (pin "14") (pinfunction "NC_14") (pintype "passive+no_connect"))
    )
    (net (code "165") (name "unconnected-(U3-NC-Pad15)") (class "Default")
      (node (ref "U3") (pin "15") (pinfunction "NC_15") (pintype "passive+no_connect"))
    )
    (net (code "166") (name "unconnected-(U3-NC-Pad16)") (class "Default")
      (node (ref "U3") (pin "16") (pinfunction "NC_16") (pintype "passive+no_connect"))
    )
    (net (code "167") (name "unconnected-(U3-NC-Pad17)") (class "Default")
      (node (ref "U3") (pin "17") (pinfunction "NC_17") (pintype "passive+no_connect"))
    )
    (net (code "168") (name "unconnected-(U3-NC-Pad18)") (class "Default")
      (node (ref "U3") (pin "18") (pinfunction "NC_18") (pintype "passive+no_connect"))
    )
    (net (code "169") (name "unconnected-(U3-NC-Pad19)") (class "Default")
      (node (ref "U3") (pin "19") (pinfunction "NC_19") (pintype "passive+no_connect"))
    )
    (net (code "170") (name "unconnected-(U3-NC-Pad20)") (class "Default")
      (node (ref "U3") (pin "20") (pinfunction "NC_20") (pintype "passive+no_connect"))
    )
    (net (code "171") (name "unconnected-(U3-NC-Pad21)") (class "Default")
      (node (ref "U3") (pin "21") (pinfunction "NC_21") (pintype "passive+no_connect"))
    )
    (net (code "172") (name "unconnected-(U3-NC-Pad22)") (class "Default")
      (node (ref "U3") (pin "22") (pinfunction "NC_22") (pintype "passive+no_connect"))
    )
    (net (code "173") (name "unconnected-(U3-R1-Pad2)") (class "Default")
      (node (ref "U3") (pin "2") (pinfunction "R1_2") (pintype "passive"))
    )
    (net (code "174") (name "unconnected-(U3-RTS-Pad24)") (class "Default")
      (node (ref "U3") (pin "24") (pinfunction "RTS_24") (pintype "passive"))
    )
    (net (code "175") (name "unconnected-(U3-SUPEND-Pad12)") (class "Default")
      (node (ref "U3") (pin "12") (pinfunction "SUPEND_12") (pintype "passive"))
    )
  )
)
